# SZ.net
KiCad netlist of a schematic drawn in Altium Designer
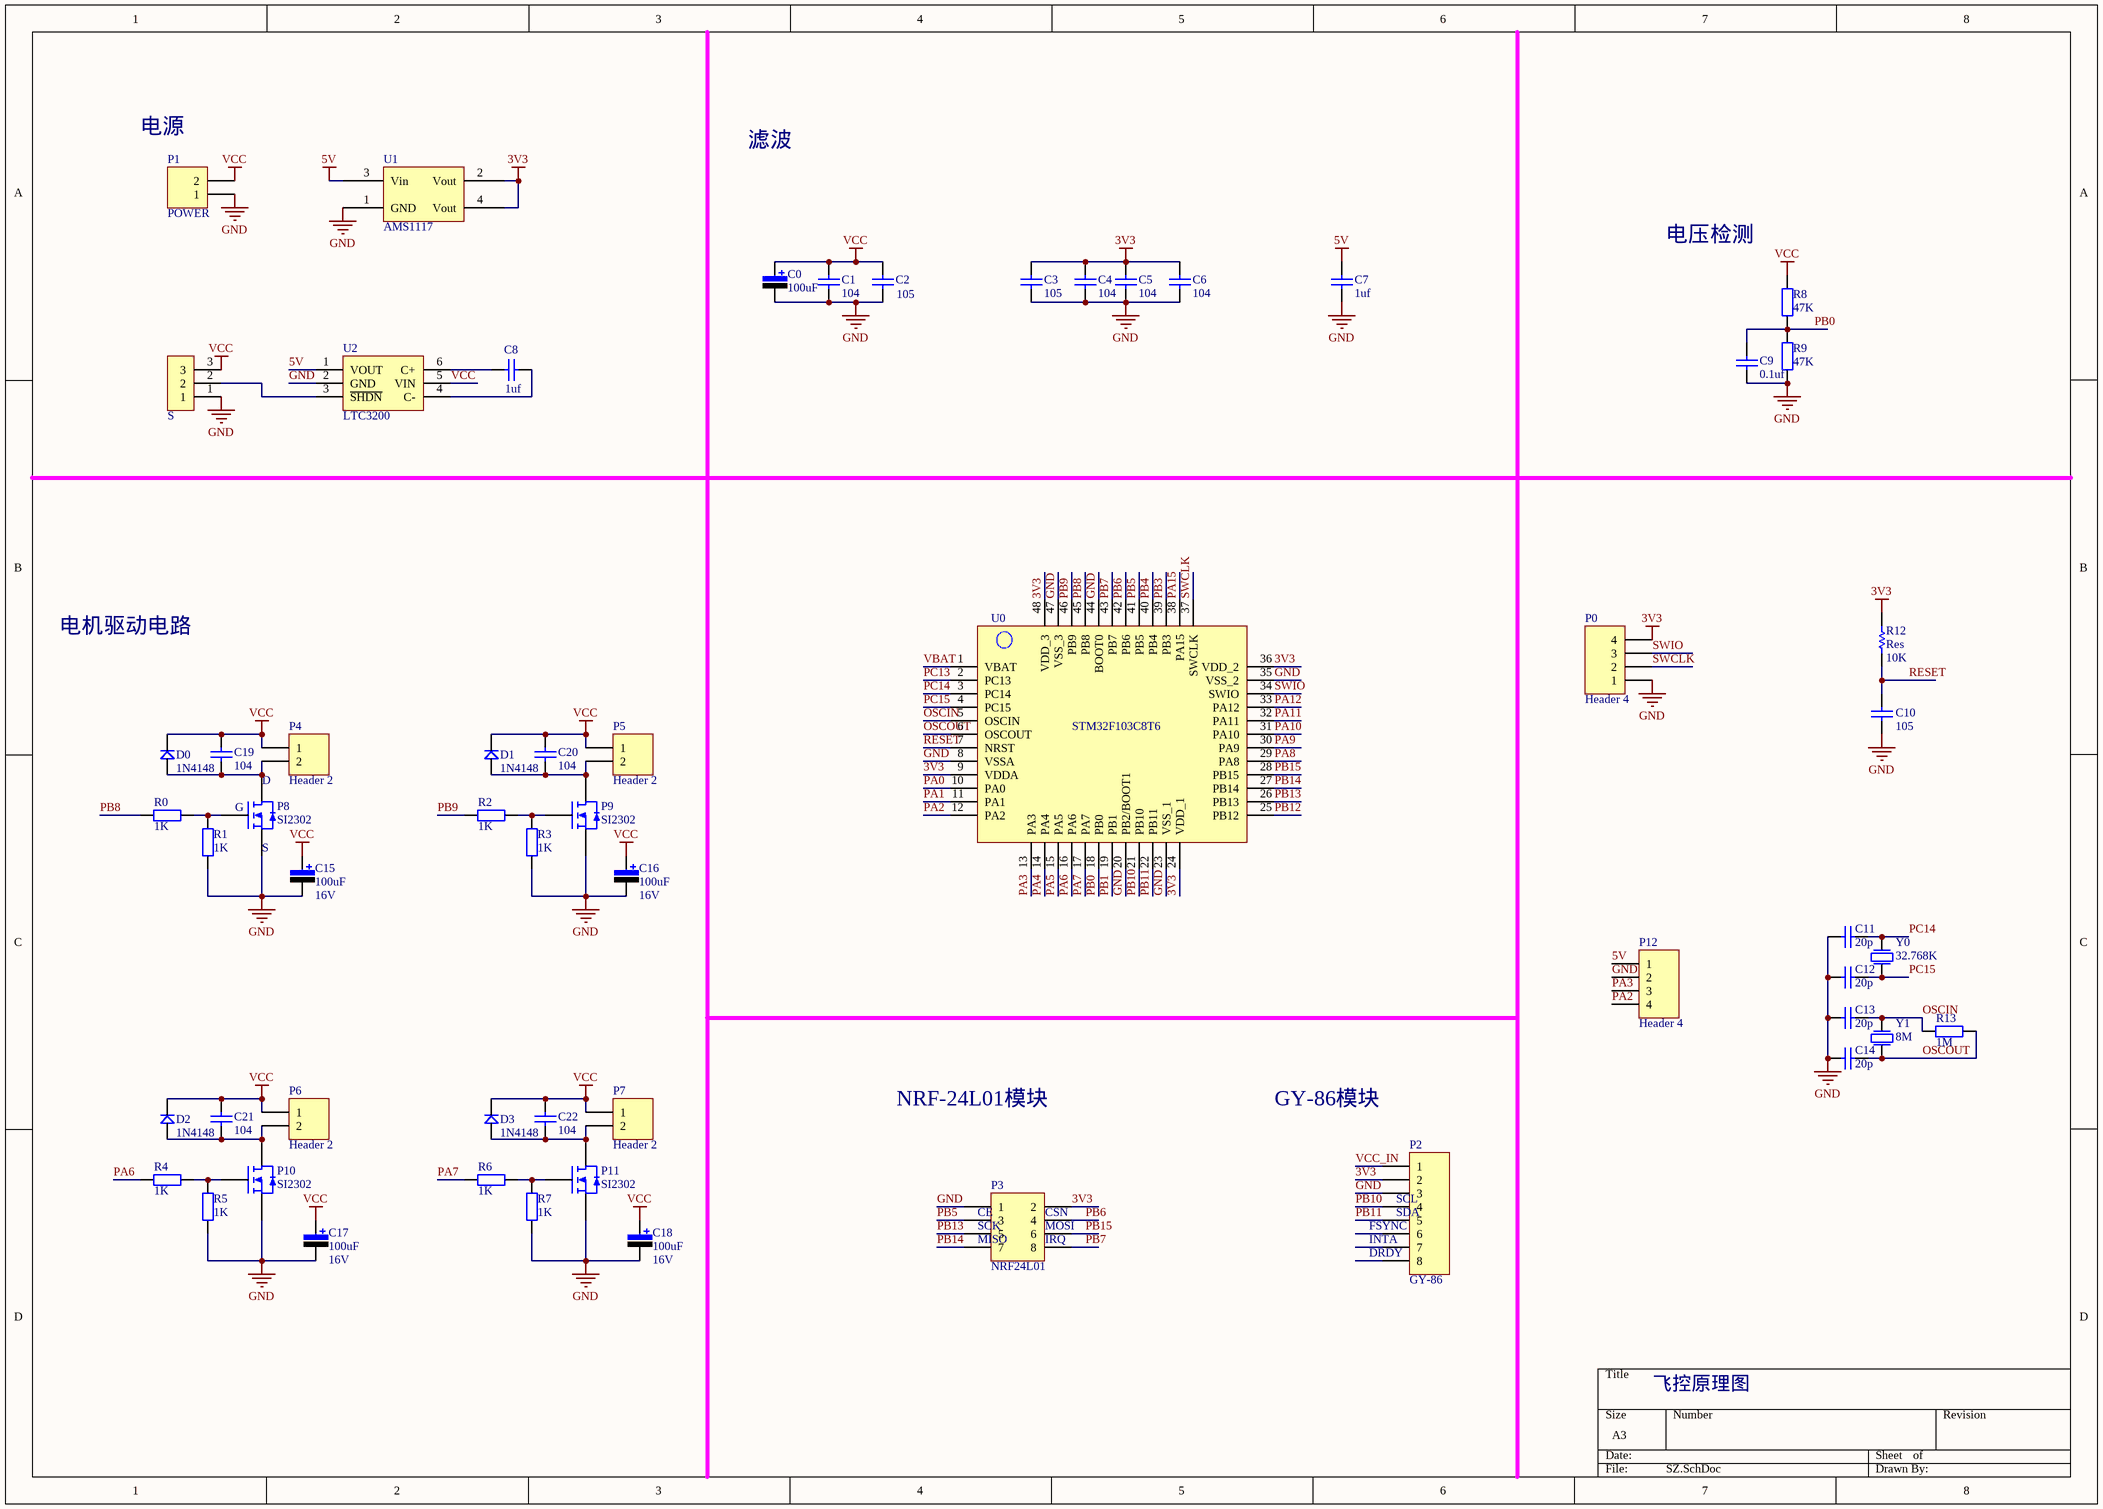
[diagram p0: SZ.SchDoc]

(export (version "E")
  (design (tool "Eeschema 10.0.6"))
  (components
    (comp (ref "C0")
      (value "100uF")
      (footprint "1206C")
      (description "极性电解电容")
      (fields (field (name "Comment") "Cap Pol") (field (name "PUBLISHER") "Altium Limited"))
      (libsource (lib "Fszhang") (part "Cap Pol"))
    )
    (comp (ref "C1")
      (value "104")
      (footprint "C0603")
      (description "Capacitor")
      (fields (field (name "PUBLISHER") "Altium Limited"))
      (libsource (lib "6-MK60DN512VLQ10") (part "CAP"))
    )
    (comp (ref "C2")
      (value "105")
      (footprint "C0603")
      (description "贴片电容")
      (fields (field (name "Comment") "Cap") (field (name "PUBLISHER") "Altium Limited"))
      (libsource (lib "插针") (part "Cap"))
    )
    (comp (ref "C3")
      (value "105")
      (footprint "C0603")
      (description "无极性电容")
      (fields (field (name "Comment") "Cap") (field (name "PUBLISHER") "Altium Limited"))
      (libsource (lib "Fszhang") (part "Cap"))
    )
    (comp (ref "C4")
      (value "104")
      (footprint "C0603")
      (description "无极性电容")
      (fields (field (name "Comment") "Cap") (field (name "PUBLISHER") "Altium Limited"))
      (libsource (lib "Fszhang") (part "Cap"))
    )
    (comp (ref "C5")
      (value "104")
      (footprint "C0603")
      (description "无极性电容")
      (fields (field (name "Comment") "Cap") (field (name "PUBLISHER") "Altium Limited"))
      (libsource (lib "Fszhang") (part "Cap"))
    )
    (comp (ref "C6")
      (value "104")
      (footprint "C0603")
      (description "无极性电容")
      (fields (field (name "Comment") "Cap") (field (name "PUBLISHER") "Altium Limited"))
      (libsource (lib "Fszhang") (part "Cap"))
    )
    (comp (ref "C7")
      (value "1uf")
      (footprint "C0603")
      (description "无极性电容")
      (fields (field (name "Comment") "Cap") (field (name "PUBLISHER") "Altium Limited"))
      (libsource (lib "Fszhang") (part "Cap"))
    )
    (comp (ref "C8")
      (value "1uf")
      (footprint "C0603")
      (description "Capacitor")
      (fields (field (name "Comment") "Cap") (field (name "PUBLISHER") "Altium Limited"))
      (libsource (lib "Miscellaneous Devices") (part "Cap"))
    )
    (comp (ref "C9")
      (value "0.1uf")
      (footprint "C0603")
      (description "无极性电容")
      (fields (field (name "Comment") "Cap") (field (name "PUBLISHER") "Altium Limited"))
      (libsource (lib "Fszhang") (part "Cap"))
    )
    (comp (ref "C10")
      (value "105")
      (footprint "C0603")
      (description "贴片电容")
      (fields (field (name "Comment") "Cap") (field (name "PUBLISHER") "Altium Limited"))
      (libsource (lib "插针") (part "Cap"))
    )
    (comp (ref "C11")
      (value "20p")
      (footprint "C0603")
      (description "无极性电容")
      (fields (field (name "Comment") "Cap") (field (name "PUBLISHER") "Altium Limited"))
      (libsource (lib "Fszhang") (part "Cap"))
    )
    (comp (ref "C12")
      (value "20p")
      (footprint "C0603")
      (description "Capacitor")
      (fields (field (name "PUBLISHER") "Altium Limited"))
      (libsource (lib "6-MK60DN512VLQ10") (part "CAP"))
    )
    (comp (ref "C13")
      (value "20p")
      (footprint "C0603")
      (description "Capacitor")
      (fields (field (name "PUBLISHER") "Altium Limited"))
      (libsource (lib "6-MK60DN512VLQ10") (part "CAP"))
    )
    (comp (ref "C14")
      (value "20p")
      (footprint "C0603")
      (description "Capacitor")
      (fields (field (name "PUBLISHER") "Altium Limited"))
      (libsource (lib "6-MK60DN512VLQ10") (part "CAP"))
    )
    (comp (ref "C15")
      (value "100uF")
      (footprint "1206C")
      (description "极性电解电容")
      (fields
        (field (name "VOL") "16V")
        (field (name "Comment") "Cap Pol")
        (field (name "PUBLISHER") "Altium Limited")
      )
      (libsource (lib "Fszhang") (part "Cap Pol"))
    )
    (comp (ref "C16")
      (value "100uF")
      (footprint "1206C")
      (description "极性电解电容")
      (fields
        (field (name "VOL") "16V")
        (field (name "Comment") "Cap Pol")
        (field (name "PUBLISHER") "Altium Limited")
      )
      (libsource (lib "Fszhang") (part "Cap Pol"))
    )
    (comp (ref "C17")
      (value "100uF")
      (footprint "1206C")
      (description "极性电解电容")
      (fields
        (field (name "VOL") "16V")
        (field (name "Comment") "Cap Pol")
        (field (name "PUBLISHER") "Altium Limited")
      )
      (libsource (lib "Fszhang") (part "Cap Pol"))
    )
    (comp (ref "C18")
      (value "100uF")
      (footprint "1206C")
      (description "极性电解电容")
      (fields
        (field (name "VOL") "16V")
        (field (name "Comment") "Cap Pol")
        (field (name "PUBLISHER") "Altium Limited")
      )
      (libsource (lib "Fszhang") (part "Cap Pol"))
    )
    (comp (ref "C19")
      (value "104")
      (footprint "C0603")
      (description "Capacitor")
      (fields (field (name "Comment") "Cap") (field (name "PUBLISHER") "Altium Limited"))
      (libsource (lib "Miscellaneous Devices") (part "Cap"))
    )
    (comp (ref "C20")
      (value "104")
      (footprint "C0603")
      (description "Capacitor")
      (fields (field (name "PUBLISHER") "Altium Limited"))
      (libsource (lib "6-MK60DN512VLQ10") (part "CAP"))
    )
    (comp (ref "C21")
      (value "104")
      (footprint "C0603")
      (description "Capacitor")
      (fields (field (name "PUBLISHER") "Altium Limited"))
      (libsource (lib "6-MK60DN512VLQ10") (part "CAP"))
    )
    (comp (ref "C22")
      (value "104")
      (footprint "C0603")
      (description "Capacitor")
      (fields (field (name "PUBLISHER") "Altium Limited"))
      (libsource (lib "6-MK60DN512VLQ10") (part "CAP"))
    )
    (comp (ref "D0") (value "1N4148") (footprint "L0603") (libsource (lib "6-MK60DN512VLQ10") (part "D")))
    (comp (ref "D1") (value "1N4148") (footprint "L0603") (libsource (lib "6-MK60DN512VLQ10") (part "D")))
    (comp (ref "D2") (value "1N4148") (footprint "L0603") (libsource (lib "6-MK60DN512VLQ10") (part "D")))
    (comp (ref "D3") (value "1N4148") (footprint "L0603") (libsource (lib "6-MK60DN512VLQ10") (part "D")))
    (comp (ref "P0")
      (value "Header 4")
      (footprint "HDR1X4")
      (description "Header, 4-Pin")
      (fields (field (name "PUBLISHER") "Altium Limited"))
      (libsource (lib "插针") (part "Header 4"))
    )
    (comp (ref "P1")
      (value "POWER")
      (footprint "HDR1X2")
      (description "Header, 2-Pin")
      (fields (field (name "PUBLISHER") "Altium Limited"))
      (libsource (lib "插针") (part "Header 2"))
    )
    (comp (ref "P2")
      (value "GY-86")
      (footprint "HDR1X8")
      (description "Header, 8-Pin")
      (fields (field (name "PUBLISHER") "Altium Limited"))
      (libsource (lib "插针") (part "Header 8"))
    )
    (comp (ref "P3")
      (value "NRF24L01")
      (footprint "HDR2X4")
      (description "Header, 4-Pin, Dual row")
      (fields (field (name "PUBLISHER") "Altium Limited"))
      (libsource (lib "插针") (part "Header 4X2"))
    )
    (comp (ref "P4")
      (value "Header 2")
      (footprint "HDR1X2")
      (description "Header, 2-Pin")
      (fields (field (name "PUBLISHER") "Altium Limited"))
      (libsource (lib "Miscellaneous Connectors") (part "Header 2"))
    )
    (comp (ref "P5")
      (value "Header 2")
      (footprint "HDR1X2")
      (description "Header, 2-Pin")
      (fields (field (name "PUBLISHER") "Altium Limited"))
      (libsource (lib "Miscellaneous Connectors") (part "Header 2"))
    )
    (comp (ref "P6")
      (value "Header 2")
      (footprint "HDR1X2")
      (description "Header, 2-Pin")
      (fields (field (name "PUBLISHER") "Altium Limited"))
      (libsource (lib "Miscellaneous Connectors") (part "Header 2"))
    )
    (comp (ref "P7")
      (value "Header 2")
      (footprint "HDR1X2")
      (description "Header, 2-Pin")
      (fields (field (name "PUBLISHER") "Altium Limited"))
      (libsource (lib "Miscellaneous Connectors") (part "Header 2"))
    )
    (comp (ref "P8") (value "SI2302") (footprint "SOT-23B_N") (libsource (lib "XPH_UAV") (part "SI2302")))
    (comp (ref "P9") (value "SI2302") (footprint "SOT-23B_N") (libsource (lib "XPH_UAV") (part "SI2302")))
    (comp (ref "P10") (value "SI2302") (footprint "SOT-23B_N") (libsource (lib "XPH_UAV") (part "SI2302")))
    (comp (ref "P11") (value "SI2302") (footprint "SOT-23B_N") (libsource (lib "XPH_UAV") (part "SI2302")))
    (comp (ref "P12")
      (value "Header 4")
      (footprint "HDR1X4")
      (description "Header, 4-Pin")
      (fields (field (name "PUBLISHER") "Altium Limited"))
      (libsource (lib "Miscellaneous Connectors") (part "Header 4"))
    )
    (comp (ref "R0")
      (value "1K")
      (footprint "0603_R")
      (description "贴片电阻")
      (fields (field (name "Comment") "1k") (field (name "PUBLISHER") "Altium Limited"))
      (libsource (lib "") (part "Res1_2"))
    )
    (comp (ref "R1")
      (value "1K")
      (footprint "0603_R")
      (description "贴片电阻")
      (fields (field (name "PUBLISHER") "Altium Limited"))
      (libsource (lib "Fszhang") (part "Res1"))
    )
    (comp (ref "R2")
      (value "1K")
      (footprint "0603_R")
      (description "贴片电阻")
      (fields (field (name "Comment") "Res1") (field (name "PUBLISHER") "Altium Limited"))
      (libsource (lib "") (part "Res1_2"))
    )
    (comp (ref "R3")
      (value "1K")
      (footprint "0603_R")
      (description "贴片电阻")
      (fields (field (name "Comment") "Res1") (field (name "PUBLISHER") "Altium Limited"))
      (libsource (lib "Fszhang") (part "Res1"))
    )
    (comp (ref "R4")
      (value "1K")
      (footprint "0603_R")
      (description "贴片电阻")
      (fields (field (name "Comment") "Res1") (field (name "PUBLISHER") "Altium Limited"))
      (libsource (lib "") (part "Res1_1"))
    )
    (comp (ref "R5")
      (value "1K")
      (footprint "0603_R")
      (description "贴片电阻")
      (fields (field (name "Comment") "Res1") (field (name "PUBLISHER") "Altium Limited"))
      (libsource (lib "Fszhang") (part "Res1"))
    )
    (comp (ref "R6")
      (value "1K")
      (footprint "0603_R")
      (description "贴片电阻")
      (fields (field (name "Comment") "Res1") (field (name "PUBLISHER") "Altium Limited"))
      (libsource (lib "") (part "Res1_1"))
    )
    (comp (ref "R7")
      (value "1K")
      (footprint "0603_R")
      (description "贴片电阻")
      (fields (field (name "Comment") "Res1") (field (name "PUBLISHER") "Altium Limited"))
      (libsource (lib "Fszhang") (part "Res1"))
    )
    (comp (ref "R8")
      (value "47K")
      (footprint "0603_R")
      (description "贴片电阻")
      (fields (field (name "Comment") "Res1") (field (name "PUBLISHER") "Altium Limited"))
      (libsource (lib "Fszhang") (part "Res1"))
    )
    (comp (ref "R9")
      (value "47K")
      (footprint "0603_R")
      (description "贴片电阻")
      (fields (field (name "Comment") "Res1") (field (name "PUBLISHER") "Altium Limited"))
      (libsource (lib "Fszhang") (part "Res1"))
    )
    (comp (ref "R12")
      (value "Res")
      (footprint "0603_R")
      (description "贴片电阻")
      (fields (field (name "ALTIUM_VALUE") "10K") (field (name "PUBLISHER") "Altium Limited"))
      (libsource (lib "插针") (part "Res"))
    )
    (comp (ref "R13")
      (value "1M")
      (footprint "0603_R")
      (description "Resistor")
      (fields (field (name "Comment") "Res2") (field (name "PUBLISHER") "Altium Limited"))
      (libsource (lib "FS44B0") (part "Res2"))
    )
    (comp (ref "S") (value "HEADER 3") (footprint "HDR1X3") (libsource (lib "XPH_UAV") (part "HEADER 3")))
    (comp (ref "U0")
      (value "Component_1")
      (footprint "LQFP-48_7x7x05P")
      (libsource (lib "XPH_UAV") (part "Component_1"))
    )
    (comp (ref "U1") (value "AMS1117") (footprint "SOT223_N") (libsource (lib "zhangcan") (part "AMS1117")))
    (comp (ref "U2") (value "LTC3200") (footprint "SOT-23-6") (libsource (lib "XPH_UAV") (part "LTC3200")))
    (comp (ref "Y0") (value "32.768K") (footprint "HDR1X2") (libsource (lib "XPH_UAV") (part "XTAL")))
    (comp (ref "Y1") (value "8M") (footprint "XTAL-RAD-0.2") (libsource (lib "XPH_UAV") (part "XTAL")))
  )
  (nets
    (net (code "1") (name "/OSCIN") (class "Default")
      (node (ref "C13") (pin "2") (pinfunction "2_2") (pintype "passive"))
      (node (ref "R13") (pin "2") (pinfunction "2_2") (pintype "passive"))
      (node (ref "U0") (pin "5") (pinfunction "OSCIN_5") (pintype "passive"))
      (node (ref "Y1") (pin "2") (pinfunction "2_2") (pintype "passive"))
    )
    (net (code "2") (name "/OSCOUT") (class "Default")
      (node (ref "C14") (pin "2") (pinfunction "2_2") (pintype "passive"))
      (node (ref "R13") (pin "1") (pinfunction "1_1") (pintype "passive"))
      (node (ref "U0") (pin "6") (pinfunction "OSCOUT_6") (pintype "passive"))
      (node (ref "Y1") (pin "1") (pinfunction "1_1") (pintype "passive"))
    )
    (net (code "3") (name "/PA0") (class "Default")
      (node (ref "U0") (pin "10") (pinfunction "PA0_10") (pintype "passive"))
    )
    (net (code "4") (name "/PA1") (class "Default")
      (node (ref "U0") (pin "11") (pinfunction "PA1_11") (pintype "passive"))
    )
    (net (code "5") (name "/PA2") (class "Default")
      (node (ref "P12") (pin "4") (pinfunction "4_4") (pintype "passive"))
      (node (ref "U0") (pin "12") (pinfunction "PA2_12") (pintype "passive"))
    )
    (net (code "6") (name "/PA3") (class "Default")
      (node (ref "P12") (pin "3") (pinfunction "3_3") (pintype "passive"))
      (node (ref "U0") (pin "13") (pinfunction "PA3_13") (pintype "passive"))
    )
    (net (code "7") (name "/PA4") (class "Default")
      (node (ref "U0") (pin "14") (pinfunction "PA4_14") (pintype "passive"))
    )
    (net (code "8") (name "/PA5") (class "Default")
      (node (ref "U0") (pin "15") (pinfunction "PA5_15") (pintype "passive"))
    )
    (net (code "9") (name "/PA6") (class "Default")
      (node (ref "R4") (pin "2") (pinfunction "2_2") (pintype "passive"))
      (node (ref "U0") (pin "16") (pinfunction "PA6_16") (pintype "passive"))
    )
    (net (code "10") (name "/PA7") (class "Default")
      (node (ref "R6") (pin "2") (pinfunction "2_2") (pintype "passive"))
      (node (ref "U0") (pin "17") (pinfunction "PA7_17") (pintype "passive"))
    )
    (net (code "11") (name "/PA8") (class "Default")
      (node (ref "U0") (pin "29") (pinfunction "PA8_29") (pintype "passive"))
    )
    (net (code "12") (name "/PA9") (class "Default")
      (node (ref "U0") (pin "30") (pinfunction "PA9_30") (pintype "passive"))
    )
    (net (code "13") (name "/PA10") (class "Default")
      (node (ref "U0") (pin "31") (pinfunction "PA10_31") (pintype "passive"))
    )
    (net (code "14") (name "/PA11") (class "Default")
      (node (ref "U0") (pin "32") (pinfunction "PA11_32") (pintype "passive"))
    )
    (net (code "15") (name "/PA12") (class "Default")
      (node (ref "U0") (pin "33") (pinfunction "PA12_33") (pintype "passive"))
    )
    (net (code "16") (name "/PA15") (class "Default")
      (node (ref "U0") (pin "38") (pinfunction "PA15_38") (pintype "passive"))
    )
    (net (code "17") (name "/PB0") (class "Default")
      (node (ref "C9") (pin "2") (pinfunction "2_2") (pintype "passive"))
      (node (ref "R8") (pin "1") (pinfunction "1_1") (pintype "passive"))
      (node (ref "R9") (pin "2") (pinfunction "2_2") (pintype "passive"))
      (node (ref "U0") (pin "18") (pinfunction "PB0_18") (pintype "passive"))
    )
    (net (code "18") (name "/PB1") (class "Default")
      (node (ref "U0") (pin "19") (pinfunction "PB1_19") (pintype "passive"))
    )
    (net (code "19") (name "/PB3") (class "Default")
      (node (ref "U0") (pin "39") (pinfunction "PB3_39") (pintype "passive"))
    )
    (net (code "20") (name "/PB4") (class "Default")
      (node (ref "U0") (pin "40") (pinfunction "PB4_40") (pintype "passive"))
    )
    (net (code "21") (name "/PB5") (class "Default")
      (node (ref "P3") (pin "3") (pinfunction "3_3") (pintype "passive"))
      (node (ref "U0") (pin "41") (pinfunction "PB5_41") (pintype "passive"))
    )
    (net (code "22") (name "/PB6") (class "Default")
      (node (ref "P3") (pin "4") (pinfunction "4_4") (pintype "passive"))
      (node (ref "U0") (pin "42") (pinfunction "PB6_42") (pintype "passive"))
    )
    (net (code "23") (name "/PB7") (class "Default")
      (node (ref "P3") (pin "8") (pinfunction "8_8") (pintype "passive"))
      (node (ref "U0") (pin "43") (pinfunction "PB7_43") (pintype "passive"))
    )
    (net (code "24") (name "/PB8") (class "Default")
      (node (ref "R0") (pin "1") (pinfunction "1_1") (pintype "passive"))
      (node (ref "U0") (pin "45") (pinfunction "PB8_45") (pintype "passive"))
    )
    (net (code "25") (name "/PB9") (class "Default")
      (node (ref "R2") (pin "1") (pinfunction "1_1") (pintype "passive"))
      (node (ref "U0") (pin "46") (pinfunction "PB9_46") (pintype "passive"))
    )
    (net (code "26") (name "/PB10") (class "Default")
      (node (ref "P2") (pin "4") (pinfunction "4_4") (pintype "passive"))
      (node (ref "U0") (pin "21") (pinfunction "PB10_21") (pintype "passive"))
    )
    (net (code "27") (name "/PB11") (class "Default")
      (node (ref "P2") (pin "5") (pinfunction "5_5") (pintype "passive"))
      (node (ref "U0") (pin "22") (pinfunction "PB11_22") (pintype "passive"))
    )
    (net (code "28") (name "/PB12") (class "Default")
      (node (ref "U0") (pin "25") (pinfunction "PB12_25") (pintype "passive"))
    )
    (net (code "29") (name "/PB13") (class "Default")
      (node (ref "P3") (pin "5") (pinfunction "5_5") (pintype "passive"))
      (node (ref "U0") (pin "26") (pinfunction "PB13_26") (pintype "passive"))
    )
    (net (code "30") (name "/PB14") (class "Default")
      (node (ref "P3") (pin "7") (pinfunction "7_7") (pintype "passive"))
      (node (ref "U0") (pin "27") (pinfunction "PB14_27") (pintype "passive"))
    )
    (net (code "31") (name "/PB15") (class "Default")
      (node (ref "P3") (pin "6") (pinfunction "6_6") (pintype "passive"))
      (node (ref "U0") (pin "28") (pinfunction "PB15_28") (pintype "passive"))
    )
    (net (code "32") (name "/PC13") (class "Default")
      (node (ref "U0") (pin "2") (pinfunction "PC13_2") (pintype "passive"))
    )
    (net (code "33") (name "/PC14") (class "Default")
      (node (ref "C11") (pin "2") (pinfunction "2_2") (pintype "passive"))
      (node (ref "U0") (pin "3") (pinfunction "PC14_3") (pintype "passive"))
      (node (ref "Y0") (pin "2") (pinfunction "2_2") (pintype "passive"))
    )
    (net (code "34") (name "/PC15") (class "Default")
      (node (ref "C12") (pin "2") (pinfunction "2_2") (pintype "passive"))
      (node (ref "U0") (pin "4") (pinfunction "PC15_4") (pintype "passive"))
      (node (ref "Y0") (pin "1") (pinfunction "1_1") (pintype "passive"))
    )
    (net (code "35") (name "/RESET") (class "Default")
      (node (ref "C10") (pin "2") (pinfunction "2_2") (pintype "passive"))
      (node (ref "R12") (pin "1") (pinfunction "1_1") (pintype "passive"))
      (node (ref "U0") (pin "7") (pinfunction "NRST_7") (pintype "passive"))
    )
    (net (code "36") (name "/SWCLK") (class "Default")
      (node (ref "P0") (pin "2") (pinfunction "2_2") (pintype "passive"))
      (node (ref "U0") (pin "37") (pinfunction "SWCLK_37") (pintype "passive"))
    )
    (net (code "37") (name "/SWIO") (class "Default")
      (node (ref "P0") (pin "3") (pinfunction "3_3") (pintype "passive"))
      (node (ref "U0") (pin "34") (pinfunction "SWIO_34") (pintype "passive"))
    )
    (net (code "38") (name "/VBAT") (class "Default")
      (node (ref "U0") (pin "1") (pinfunction "VBAT_1") (pintype "passive"))
    )
    (net (code "39") (name "/VCC_IN") (class "Default")
      (node (ref "P2") (pin "1") (pinfunction "1_1") (pintype "passive"))
    )
    (net (code "40") (name "3V3") (class "Default")
      (node (ref "C3") (pin "2") (pinfunction "2_2") (pintype "passive"))
      (node (ref "C4") (pin "2") (pinfunction "2_2") (pintype "passive"))
      (node (ref "C5") (pin "2") (pinfunction "2_2") (pintype "passive"))
      (node (ref "C6") (pin "2") (pinfunction "2_2") (pintype "passive"))
      (node (ref "P0") (pin "4") (pinfunction "4_4") (pintype "passive"))
      (node (ref "P2") (pin "2") (pinfunction "2_2") (pintype "passive"))
      (node (ref "P3") (pin "2") (pinfunction "2_2") (pintype "passive"))
      (node (ref "R12") (pin "2") (pinfunction "2_2") (pintype "passive"))
      (node (ref "U0") (pin "24") (pinfunction "VDD_1_24") (pintype "passive"))
      (node (ref "U0") (pin "36") (pinfunction "VDD_2_36") (pintype "passive"))
      (node (ref "U0") (pin "48") (pinfunction "VDD_3_48") (pintype "passive"))
      (node (ref "U0") (pin "9") (pinfunction "VDDA_9") (pintype "passive"))
      (node (ref "U1") (pin "2") (pinfunction "Vout_2") (pintype "passive"))
      (node (ref "U1") (pin "4") (pinfunction "Vout_4") (pintype "passive"))
    )
    (net (code "41") (name "5V") (class "Default")
      (node (ref "C7") (pin "1") (pinfunction "1_1") (pintype "passive"))
      (node (ref "P12") (pin "1") (pinfunction "1_1") (pintype "passive"))
      (node (ref "U1") (pin "3") (pinfunction "Vin_3") (pintype "passive"))
      (node (ref "U2") (pin "1") (pinfunction "VOUT_1") (pintype "passive"))
    )
    (net (code "42") (name "GND") (class "Default")
      (node (ref "C0") (pin "2") (pinfunction "2_2") (pintype "passive"))
      (node (ref "C1") (pin "1") (pinfunction "1_1") (pintype "passive"))
      (node (ref "C10") (pin "1") (pinfunction "1_1") (pintype "passive"))
      (node (ref "C11") (pin "1") (pinfunction "1_1") (pintype "passive"))
      (node (ref "C12") (pin "1") (pinfunction "1_1") (pintype "passive"))
      (node (ref "C13") (pin "1") (pinfunction "1_1") (pintype "passive"))
      (node (ref "C14") (pin "1") (pinfunction "1_1") (pintype "passive"))
      (node (ref "C15") (pin "2") (pinfunction "2_2") (pintype "passive"))
      (node (ref "C16") (pin "2") (pinfunction "2_2") (pintype "passive"))
      (node (ref "C17") (pin "2") (pinfunction "2_2") (pintype "passive"))
      (node (ref "C18") (pin "2") (pinfunction "2_2") (pintype "passive"))
      (node (ref "C2") (pin "2") (pinfunction "2_2") (pintype "passive"))
      (node (ref "C3") (pin "1") (pinfunction "1_1") (pintype "passive"))
      (node (ref "C4") (pin "1") (pinfunction "1_1") (pintype "passive"))
      (node (ref "C5") (pin "1") (pinfunction "1_1") (pintype "passive"))
      (node (ref "C6") (pin "1") (pinfunction "1_1") (pintype "passive"))
      (node (ref "C7") (pin "2") (pinfunction "2_2") (pintype "passive"))
      (node (ref "C9") (pin "1") (pinfunction "1_1") (pintype "passive"))
      (node (ref "P0") (pin "1") (pinfunction "1_1") (pintype "passive"))
      (node (ref "P1") (pin "1") (pinfunction "1_1") (pintype "passive"))
      (node (ref "P10") (pin "2") (pinfunction "2_2") (pintype "passive"))
      (node (ref "P11") (pin "2") (pinfunction "2_2") (pintype "passive"))
      (node (ref "P12") (pin "2") (pinfunction "2_2") (pintype "passive"))
      (node (ref "P2") (pin "3") (pinfunction "3_3") (pintype "passive"))
      (node (ref "P3") (pin "1") (pinfunction "1_1") (pintype "passive"))
      (node (ref "P8") (pin "2") (pinfunction "2_2") (pintype "passive"))
      (node (ref "P9") (pin "2") (pinfunction "2_2") (pintype "passive"))
      (node (ref "R1") (pin "1") (pinfunction "1_1") (pintype "passive"))
      (node (ref "R3") (pin "1") (pinfunction "1_1") (pintype "passive"))
      (node (ref "R5") (pin "1") (pinfunction "1_1") (pintype "passive"))
      (node (ref "R7") (pin "1") (pinfunction "1_1") (pintype "passive"))
      (node (ref "R9") (pin "1") (pinfunction "1_1") (pintype "passive"))
      (node (ref "S") (pin "1") (pinfunction "1_1") (pintype "passive"))
      (node (ref "U0") (pin "20") (pinfunction "PB2/BOOT1_20") (pintype "passive"))
      (node (ref "U0") (pin "23") (pinfunction "VSS_1_23") (pintype "passive"))
      (node (ref "U0") (pin "35") (pinfunction "VSS_2_35") (pintype "passive"))
      (node (ref "U0") (pin "44") (pinfunction "BOOT0_44") (pintype "passive"))
      (node (ref "U0") (pin "47") (pinfunction "VSS_3_47") (pintype "passive"))
      (node (ref "U0") (pin "8") (pinfunction "VSSA_8") (pintype "passive"))
      (node (ref "U1") (pin "1") (pinfunction "GND_1") (pintype "passive"))
      (node (ref "U2") (pin "2") (pinfunction "GND_2") (pintype "passive"))
    )
    (net (code "43") (name "Net-(C19-Pad2)") (class "Default")
      (node (ref "C19") (pin "2") (pinfunction "2_2") (pintype "passive"))
      (node (ref "D0") (pin "1") (pintype "passive"))
      (node (ref "P4") (pin "2") (pinfunction "2_2") (pintype "passive"))
      (node (ref "P8") (pin "3") (pinfunction "3_3") (pintype "passive"))
    )
    (net (code "44") (name "Net-(C20-Pad1)") (class "Default")
      (node (ref "C20") (pin "1") (pinfunction "1_1") (pintype "passive"))
      (node (ref "D1") (pin "1") (pintype "passive"))
      (node (ref "P5") (pin "2") (pinfunction "2_2") (pintype "passive"))
      (node (ref "P9") (pin "3") (pinfunction "3_3") (pintype "passive"))
    )
    (net (code "45") (name "Net-(C21-Pad1)") (class "Default")
      (node (ref "C21") (pin "1") (pinfunction "1_1") (pintype "passive"))
      (node (ref "D2") (pin "1") (pintype "passive"))
      (node (ref "P10") (pin "3") (pinfunction "3_3") (pintype "passive"))
      (node (ref "P6") (pin "2") (pinfunction "2_2") (pintype "passive"))
    )
    (net (code "46") (name "Net-(C22-Pad1)") (class "Default")
      (node (ref "C22") (pin "1") (pinfunction "1_1") (pintype "passive"))
      (node (ref "D3") (pin "1") (pintype "passive"))
      (node (ref "P11") (pin "3") (pinfunction "3_3") (pintype "passive"))
      (node (ref "P7") (pin "2") (pinfunction "2_2") (pintype "passive"))
    )
    (net (code "47") (name "Net-(P8-Pad1)") (class "Default")
      (node (ref "P8") (pin "1") (pinfunction "1_1") (pintype "passive"))
      (node (ref "R0") (pin "2") (pinfunction "2_2") (pintype "passive"))
      (node (ref "R1") (pin "2") (pinfunction "2_2") (pintype "passive"))
    )
    (net (code "48") (name "Net-(P9-Pad1)") (class "Default")
      (node (ref "P9") (pin "1") (pinfunction "1_1") (pintype "passive"))
      (node (ref "R2") (pin "2") (pinfunction "2_2") (pintype "passive"))
      (node (ref "R3") (pin "2") (pinfunction "2_2") (pintype "passive"))
    )
    (net (code "49") (name "Net-(P10-Pad1)") (class "Default")
      (node (ref "P10") (pin "1") (pinfunction "1_1") (pintype "passive"))
      (node (ref "R4") (pin "1") (pinfunction "1_1") (pintype "passive"))
      (node (ref "R5") (pin "2") (pinfunction "2_2") (pintype "passive"))
    )
    (net (code "50") (name "Net-(P11-Pad1)") (class "Default")
      (node (ref "P11") (pin "1") (pinfunction "1_1") (pintype "passive"))
      (node (ref "R6") (pin "1") (pinfunction "1_1") (pintype "passive"))
      (node (ref "R7") (pin "2") (pinfunction "2_2") (pintype "passive"))
    )
    (net (code "51") (name "Net-(U2-C+)") (class "Default")
      (node (ref "C8") (pin "1") (pinfunction "1_1") (pintype "passive"))
      (node (ref "U2") (pin "6") (pinfunction "C+_6") (pintype "passive"))
    )
    (net (code "52") (name "Net-(U2-C-)") (class "Default")
      (node (ref "C8") (pin "2") (pinfunction "2_2") (pintype "passive"))
      (node (ref "U2") (pin "4") (pinfunction "C-_4") (pintype "passive"))
    )
    (net (code "53") (name "Net-(U2-~{SHDN})") (class "Default")
      (node (ref "S") (pin "2") (pinfunction "2_2") (pintype "passive"))
      (node (ref "U2") (pin "3") (pinfunction "~{SHDN}_3") (pintype "passive"))
    )
    (net (code "54") (name "VCC") (class "Default")
      (node (ref "C0") (pin "1") (pinfunction "1_1") (pintype "passive"))
      (node (ref "C1") (pin "2") (pinfunction "2_2") (pintype "passive"))
      (node (ref "C15") (pin "1") (pinfunction "1_1") (pintype "passive"))
      (node (ref "C16") (pin "1") (pinfunction "1_1") (pintype "passive"))
      (node (ref "C17") (pin "1") (pinfunction "1_1") (pintype "passive"))
      (node (ref "C18") (pin "1") (pinfunction "1_1") (pintype "passive"))
      (node (ref "C19") (pin "1") (pinfunction "1_1") (pintype "passive"))
      (node (ref "C2") (pin "1") (pinfunction "1_1") (pintype "passive"))
      (node (ref "C20") (pin "2") (pinfunction "2_2") (pintype "passive"))
      (node (ref "C21") (pin "2") (pinfunction "2_2") (pintype "passive"))
      (node (ref "C22") (pin "2") (pinfunction "2_2") (pintype "passive"))
      (node (ref "D0") (pin "2") (pintype "passive"))
      (node (ref "D1") (pin "2") (pintype "passive"))
      (node (ref "D2") (pin "2") (pintype "passive"))
      (node (ref "D3") (pin "2") (pintype "passive"))
      (node (ref "P1") (pin "2") (pinfunction "2_2") (pintype "passive"))
      (node (ref "P4") (pin "1") (pinfunction "1_1") (pintype "passive"))
      (node (ref "P5") (pin "1") (pinfunction "1_1") (pintype "passive"))
      (node (ref "P6") (pin "1") (pinfunction "1_1") (pintype "passive"))
      (node (ref "P7") (pin "1") (pinfunction "1_1") (pintype "passive"))
      (node (ref "R8") (pin "2") (pinfunction "2_2") (pintype "passive"))
      (node (ref "S") (pin "3") (pinfunction "3_3") (pintype "passive"))
      (node (ref "U2") (pin "5") (pinfunction "VIN_5") (pintype "passive"))
    )
    (net (code "55") (name "unconnected-(P2-Pad6)") (class "Default")
      (node (ref "P2") (pin "6") (pinfunction "6_6") (pintype "passive"))
    )
    (net (code "56") (name "unconnected-(P2-Pad7)") (class "Default")
      (node (ref "P2") (pin "7") (pinfunction "7_7") (pintype "passive"))
    )
    (net (code "57") (name "unconnected-(P2-Pad8)") (class "Default")
      (node (ref "P2") (pin "8") (pinfunction "8_8") (pintype "passive"))
    )
  )
)
